# Arduino_AMRSID_tester_dual.net
KiCad netlist of a schematic drawn in EAGLE
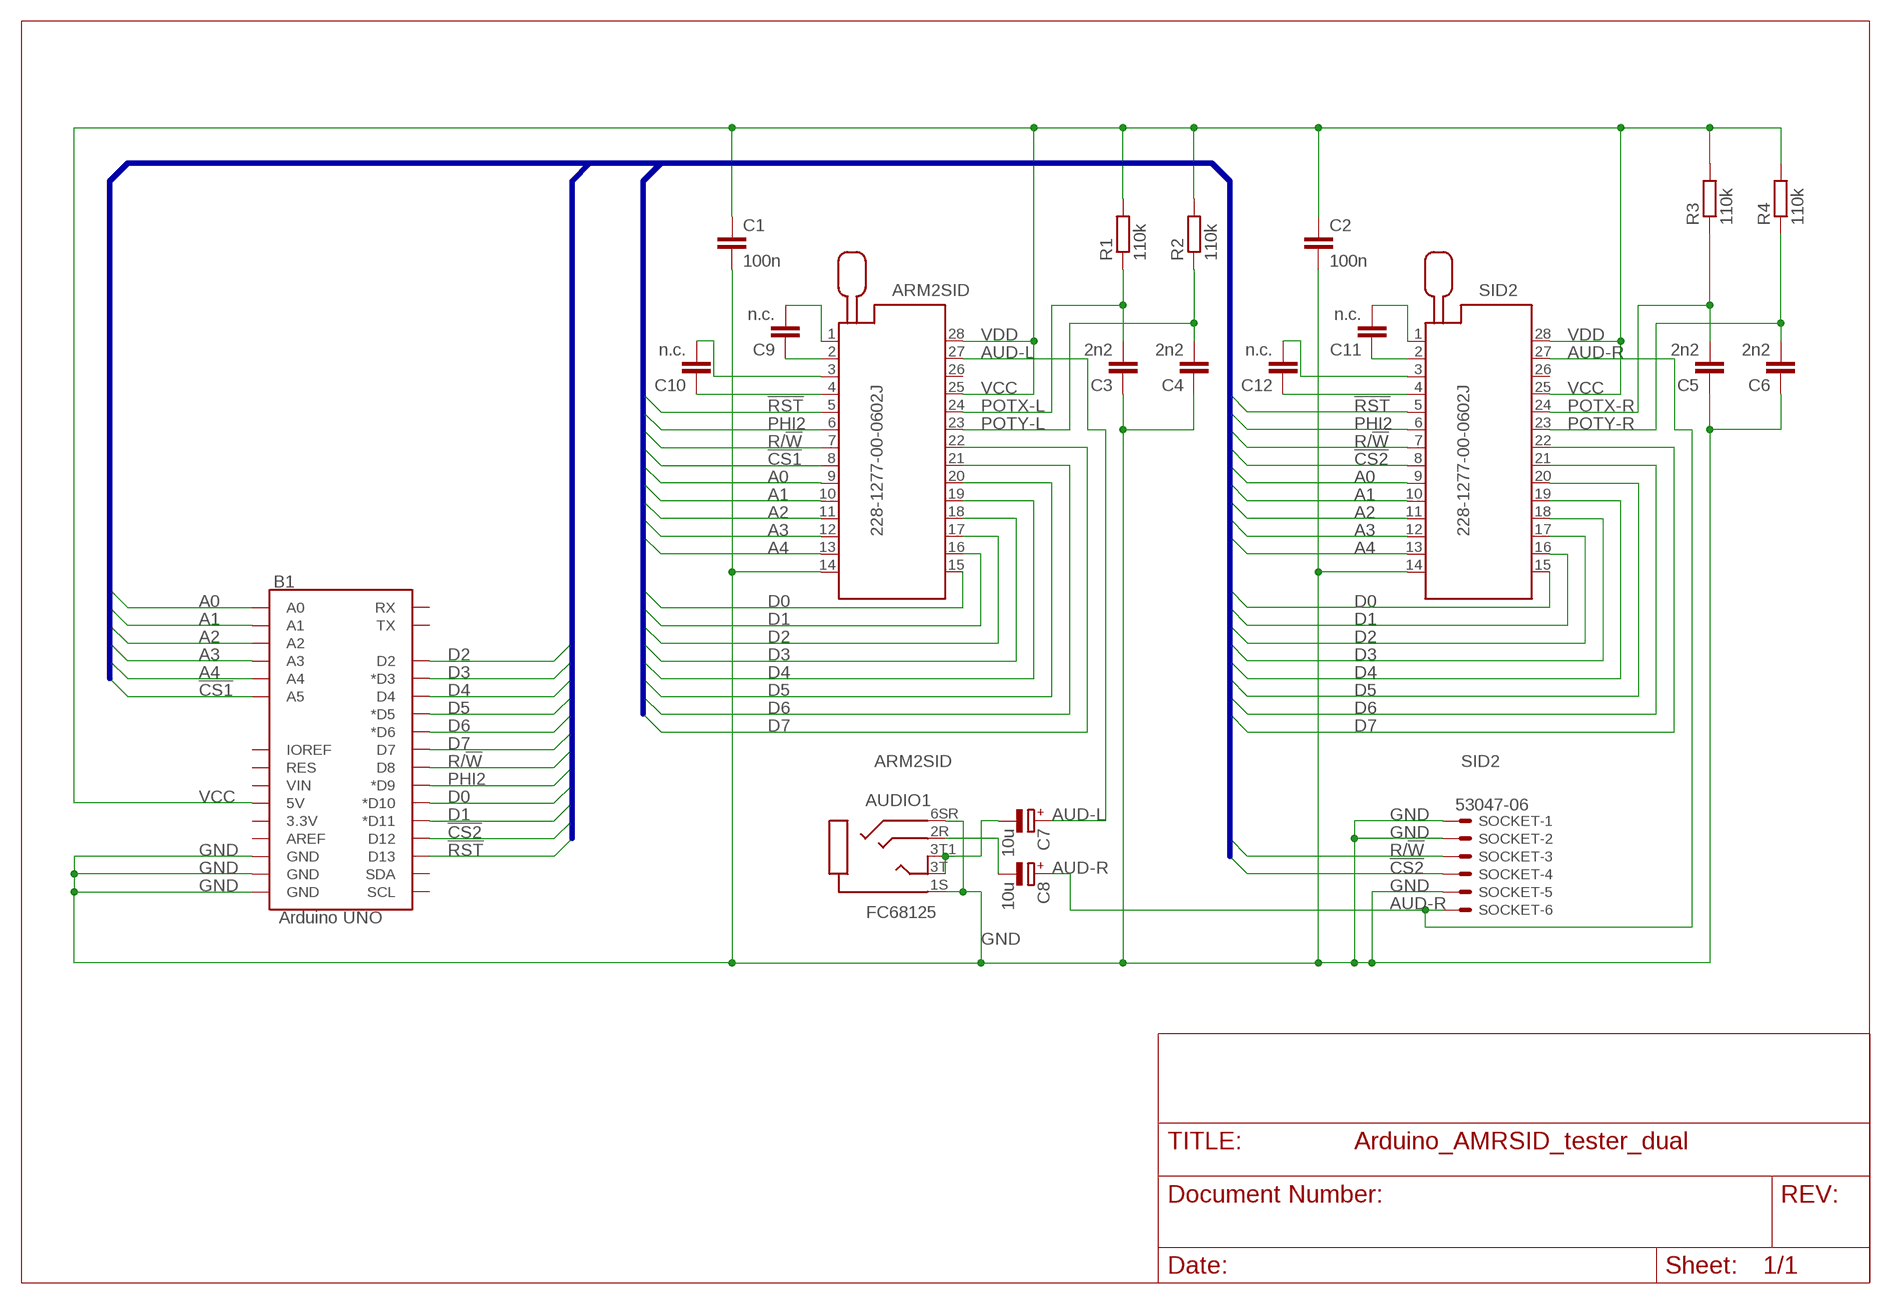
[diagram p0: schematic, sheet 1]

(export (version "E")
  (design (tool "Eeschema 10.0.6"))
  (components
    (comp (ref "ARM2SID")
      (value "228-1277-00-0602J")
      (footprint "eagle-import:228-1277-00-0602J")
      (fields (field (name "MF") "3M"))
      (libsource (lib "eagle-import") (part "228-?00-0602J1277-"))
    )
    (comp (ref "AUDIO1")
      (value "FC68125")
      (footprint "eagle-import:FC68125")
      (libsource (lib "eagle-import") (part "FC68125"))
    )
    (comp (ref "B1")
      (value "Arduino UNO")
      (footprint "eagle-import:UNO_R3_SHIELD")
      (libsource (lib "eagle-import") (part "ARDUINO_UNO_R3_SHIELDBASIC"))
    )
    (comp (ref "C1")
      (value "100n")
      (footprint "eagle-import:C0805K")
      (libsource (lib "eagle-import") (part "C-EUC0805K"))
    )
    (comp (ref "C2")
      (value "100n")
      (footprint "eagle-import:C0805K")
      (libsource (lib "eagle-import") (part "C-EUC0805K"))
    )
    (comp (ref "C3")
      (value "2n2")
      (footprint "eagle-import:C0805K")
      (libsource (lib "eagle-import") (part "C-EUC0805K"))
    )
    (comp (ref "C4")
      (value "2n2")
      (footprint "eagle-import:C0805K")
      (libsource (lib "eagle-import") (part "C-EUC0805K"))
    )
    (comp (ref "C5")
      (value "2n2")
      (footprint "eagle-import:C0805K")
      (libsource (lib "eagle-import") (part "C-EUC0805K"))
    )
    (comp (ref "C6")
      (value "2n2")
      (footprint "eagle-import:C0805K")
      (libsource (lib "eagle-import") (part "C-EUC0805K"))
    )
    (comp (ref "C7")
      (value "10u")
      (footprint "eagle-import:B_3528-21R")
      (libsource (lib "eagle-import") (part "CPOL-EUB/3528-21R"))
    )
    (comp (ref "C8")
      (value "10u")
      (footprint "eagle-import:B_3528-21R")
      (libsource (lib "eagle-import") (part "CPOL-EUB/3528-21R"))
    )
    (comp (ref "C9")
      (value "n.c.")
      (footprint "eagle-import:C0805K")
      (libsource (lib "eagle-import") (part "C-EUC0805K"))
    )
    (comp (ref "C10")
      (value "n.c.")
      (footprint "eagle-import:C0805K")
      (libsource (lib "eagle-import") (part "C-EUC0805K"))
    )
    (comp (ref "C11")
      (value "n.c.")
      (footprint "eagle-import:C0805K")
      (libsource (lib "eagle-import") (part "C-EUC0805K"))
    )
    (comp (ref "C12")
      (value "n.c.")
      (footprint "eagle-import:C0805K")
      (libsource (lib "eagle-import") (part "C-EUC0805K"))
    )
    (comp (ref "R1")
      (value "110k")
      (footprint "eagle-import:R0805")
      (libsource (lib "eagle-import") (part "R-EU_R0805"))
    )
    (comp (ref "R2")
      (value "110k")
      (footprint "eagle-import:R0805")
      (libsource (lib "eagle-import") (part "R-EU_R0805"))
    )
    (comp (ref "R3")
      (value "110k")
      (footprint "eagle-import:R0805")
      (libsource (lib "eagle-import") (part "R-EU_R0805"))
    )
    (comp (ref "R4")
      (value "110k")
      (footprint "eagle-import:R0805")
      (libsource (lib "eagle-import") (part "R-EU_R0805"))
    )
    (comp (ref "SID2")
      (value "228-1277-00-0602J")
      (footprint "eagle-import:228-1277-00-0602J")
      (fields (field (name "MF") "3M"))
      (libsource (lib "eagle-import") (part "228-?00-0602J1277-"))
    )
    (comp (ref "SOCKET")
      (value "53047-06")
      (footprint "eagle-import:53047-06")
      (fields (field (name "MPN") "53047-0610-C"))
      (libsource (lib "eagle-import") (part "53?-06047"))
    )
  )
  (nets
    (net (code "1") (name "/A0") (class "Default")
      (node (ref "ARM2SID") (pin "9") (pinfunction "9_9") (pintype "passive"))
      (node (ref "B1") (pin "A0") (pinfunction "A0_A0") (pintype "bidirectional"))
      (node (ref "SID2") (pin "9") (pinfunction "9_9") (pintype "passive"))
    )
    (net (code "2") (name "/A1") (class "Default")
      (node (ref "ARM2SID") (pin "10") (pinfunction "10_10") (pintype "passive"))
      (node (ref "B1") (pin "A1") (pinfunction "A1_A1") (pintype "bidirectional"))
      (node (ref "SID2") (pin "10") (pinfunction "10_10") (pintype "passive"))
    )
    (net (code "3") (name "/A2") (class "Default")
      (node (ref "ARM2SID") (pin "11") (pinfunction "11_11") (pintype "passive"))
      (node (ref "B1") (pin "A2") (pinfunction "A2_A2") (pintype "bidirectional"))
      (node (ref "SID2") (pin "11") (pinfunction "11_11") (pintype "passive"))
    )
    (net (code "4") (name "/A3") (class "Default")
      (node (ref "ARM2SID") (pin "12") (pinfunction "12_12") (pintype "passive"))
      (node (ref "B1") (pin "A3") (pinfunction "A3_A3") (pintype "bidirectional"))
      (node (ref "SID2") (pin "12") (pinfunction "12_12") (pintype "passive"))
    )
    (net (code "5") (name "/A4") (class "Default")
      (node (ref "ARM2SID") (pin "13") (pinfunction "13_13") (pintype "passive"))
      (node (ref "B1") (pin "A4") (pinfunction "A4_A4") (pintype "bidirectional"))
      (node (ref "SID2") (pin "13") (pinfunction "13_13") (pintype "passive"))
    )
    (net (code "6") (name "/AUD-L") (class "Default")
      (node (ref "ARM2SID") (pin "27") (pinfunction "27_27") (pintype "passive"))
      (node (ref "C7") (pin "+") (pinfunction "+_+") (pintype "passive"))
    )
    (net (code "7") (name "/AUD-R") (class "Default")
      (node (ref "C8") (pin "+") (pinfunction "+_+") (pintype "passive"))
      (node (ref "SID2") (pin "27") (pinfunction "27_27") (pintype "passive"))
      (node (ref "SOCKET") (pin "6") (pinfunction "S_6") (pintype "passive"))
    )
    (net (code "8") (name "/D0") (class "Default")
      (node (ref "ARM2SID") (pin "15") (pinfunction "15_15") (pintype "passive"))
      (node (ref "B1") (pin "D10") (pinfunction "*D10_D10") (pintype "bidirectional"))
      (node (ref "SID2") (pin "15") (pinfunction "15_15") (pintype "passive"))
    )
    (net (code "9") (name "/D1") (class "Default")
      (node (ref "ARM2SID") (pin "16") (pinfunction "16_16") (pintype "passive"))
      (node (ref "B1") (pin "D11") (pinfunction "*D11_D11") (pintype "bidirectional"))
      (node (ref "SID2") (pin "16") (pinfunction "16_16") (pintype "passive"))
    )
    (net (code "10") (name "/D2") (class "Default")
      (node (ref "ARM2SID") (pin "17") (pinfunction "17_17") (pintype "passive"))
      (node (ref "B1") (pin "D2") (pinfunction "D2_D2") (pintype "bidirectional"))
      (node (ref "SID2") (pin "17") (pinfunction "17_17") (pintype "passive"))
    )
    (net (code "11") (name "/D3") (class "Default")
      (node (ref "ARM2SID") (pin "18") (pinfunction "18_18") (pintype "passive"))
      (node (ref "B1") (pin "D3") (pinfunction "*D3_D3") (pintype "bidirectional"))
      (node (ref "SID2") (pin "18") (pinfunction "18_18") (pintype "passive"))
    )
    (net (code "12") (name "/D4") (class "Default")
      (node (ref "ARM2SID") (pin "19") (pinfunction "19_19") (pintype "passive"))
      (node (ref "B1") (pin "D4") (pinfunction "D4_D4") (pintype "bidirectional"))
      (node (ref "SID2") (pin "19") (pinfunction "19_19") (pintype "passive"))
    )
    (net (code "13") (name "/D5") (class "Default")
      (node (ref "ARM2SID") (pin "20") (pinfunction "20_20") (pintype "passive"))
      (node (ref "B1") (pin "D5") (pinfunction "*D5_D5") (pintype "bidirectional"))
      (node (ref "SID2") (pin "20") (pinfunction "20_20") (pintype "passive"))
    )
    (net (code "14") (name "/D6") (class "Default")
      (node (ref "ARM2SID") (pin "21") (pinfunction "21_21") (pintype "passive"))
      (node (ref "B1") (pin "D6") (pinfunction "*D6_D6") (pintype "bidirectional"))
      (node (ref "SID2") (pin "21") (pinfunction "21_21") (pintype "passive"))
    )
    (net (code "15") (name "/D7") (class "Default")
      (node (ref "ARM2SID") (pin "22") (pinfunction "22_22") (pintype "passive"))
      (node (ref "B1") (pin "D7") (pinfunction "D7_D7") (pintype "bidirectional"))
      (node (ref "SID2") (pin "22") (pinfunction "22_22") (pintype "passive"))
    )
    (net (code "16") (name "/GND") (class "Default")
      (node (ref "ARM2SID") (pin "14") (pinfunction "14_14") (pintype "passive"))
      (node (ref "AUDIO1") (pin "1S") (pinfunction "1S_1S") (pintype "bidirectional"))
      (node (ref "AUDIO1") (pin "6SR") (pinfunction "6SR_6SR") (pintype "bidirectional"))
      (node (ref "B1") (pin "GND@0") (pinfunction "GND_GND@0") (pintype "bidirectional"))
      (node (ref "B1") (pin "GND@1") (pinfunction "GND_GND@1") (pintype "bidirectional"))
      (node (ref "B1") (pin "GND@2") (pinfunction "GND_GND@2") (pintype "bidirectional"))
      (node (ref "C1") (pin "2") (pinfunction "2_2") (pintype "passive"))
      (node (ref "C2") (pin "2") (pinfunction "2_2") (pintype "passive"))
      (node (ref "C3") (pin "1") (pinfunction "1_1") (pintype "passive"))
      (node (ref "C4") (pin "1") (pinfunction "1_1") (pintype "passive"))
      (node (ref "C5") (pin "1") (pinfunction "1_1") (pintype "passive"))
      (node (ref "C6") (pin "1") (pinfunction "1_1") (pintype "passive"))
      (node (ref "SID2") (pin "14") (pinfunction "14_14") (pintype "passive"))
      (node (ref "SOCKET") (pin "1") (pinfunction "S_1") (pintype "passive"))
      (node (ref "SOCKET") (pin "2") (pinfunction "S_2") (pintype "passive"))
      (node (ref "SOCKET") (pin "5") (pinfunction "S_5") (pintype "passive"))
    )
    (net (code "17") (name "/PHI2") (class "Default")
      (node (ref "ARM2SID") (pin "6") (pinfunction "6_6") (pintype "passive"))
      (node (ref "B1") (pin "D9") (pinfunction "*D9_D9") (pintype "bidirectional"))
      (node (ref "SID2") (pin "6") (pinfunction "6_6") (pintype "passive"))
    )
    (net (code "18") (name "/POTX-L") (class "Default")
      (node (ref "ARM2SID") (pin "24") (pinfunction "24_24") (pintype "passive"))
      (node (ref "C3") (pin "2") (pinfunction "2_2") (pintype "passive"))
      (node (ref "R1") (pin "1") (pinfunction "1_1") (pintype "passive"))
    )
    (net (code "19") (name "/POTX-R") (class "Default")
      (node (ref "C5") (pin "2") (pinfunction "2_2") (pintype "passive"))
      (node (ref "R3") (pin "1") (pinfunction "1_1") (pintype "passive"))
      (node (ref "SID2") (pin "24") (pinfunction "24_24") (pintype "passive"))
    )
    (net (code "20") (name "/POTY-L") (class "Default")
      (node (ref "ARM2SID") (pin "23") (pinfunction "23_23") (pintype "passive"))
      (node (ref "C4") (pin "2") (pinfunction "2_2") (pintype "passive"))
      (node (ref "R2") (pin "1") (pinfunction "1_1") (pintype "passive"))
    )
    (net (code "21") (name "/POTY-R") (class "Default")
      (node (ref "C6") (pin "2") (pinfunction "2_2") (pintype "passive"))
      (node (ref "R4") (pin "1") (pinfunction "1_1") (pintype "passive"))
      (node (ref "SID2") (pin "23") (pinfunction "23_23") (pintype "passive"))
    )
    (net (code "22") (name "/R{slash}~{W}") (class "Default")
      (node (ref "ARM2SID") (pin "7") (pinfunction "7_7") (pintype "passive"))
      (node (ref "B1") (pin "D8") (pinfunction "D8_D8") (pintype "bidirectional"))
      (node (ref "SID2") (pin "7") (pinfunction "7_7") (pintype "passive"))
      (node (ref "SOCKET") (pin "3") (pinfunction "S_3") (pintype "passive"))
    )
    (net (code "23") (name "/VCC") (class "Default")
      (node (ref "ARM2SID") (pin "25") (pinfunction "25_25") (pintype "passive"))
      (node (ref "ARM2SID") (pin "28") (pinfunction "28_28") (pintype "passive"))
      (node (ref "B1") (pin "5V") (pinfunction "5V_5V") (pintype "bidirectional"))
      (node (ref "C1") (pin "1") (pinfunction "1_1") (pintype "passive"))
      (node (ref "C2") (pin "1") (pinfunction "1_1") (pintype "passive"))
      (node (ref "R1") (pin "2") (pinfunction "2_2") (pintype "passive"))
      (node (ref "R2") (pin "2") (pinfunction "2_2") (pintype "passive"))
      (node (ref "R3") (pin "2") (pinfunction "2_2") (pintype "passive"))
      (node (ref "R4") (pin "2") (pinfunction "2_2") (pintype "passive"))
      (node (ref "SID2") (pin "25") (pinfunction "25_25") (pintype "passive"))
      (node (ref "SID2") (pin "28") (pinfunction "28_28") (pintype "passive"))
    )
    (net (code "24") (name "/~{CS1}") (class "Default")
      (node (ref "ARM2SID") (pin "8") (pinfunction "8_8") (pintype "passive"))
      (node (ref "B1") (pin "A5") (pinfunction "A5_A5") (pintype "bidirectional"))
    )
    (net (code "25") (name "/~{CS2}") (class "Default")
      (node (ref "B1") (pin "D12") (pinfunction "D12_D12") (pintype "bidirectional"))
      (node (ref "SID2") (pin "8") (pinfunction "8_8") (pintype "passive"))
      (node (ref "SOCKET") (pin "4") (pinfunction "S_4") (pintype "passive"))
    )
    (net (code "26") (name "/~{RST}") (class "Default")
      (node (ref "ARM2SID") (pin "5") (pinfunction "5_5") (pintype "passive"))
      (node (ref "B1") (pin "D13") (pinfunction "D13_D13") (pintype "bidirectional"))
      (node (ref "SID2") (pin "5") (pinfunction "5_5") (pintype "passive"))
    )
    (net (code "27") (name "Net-(ARM2SID-Pad1)") (class "Default")
      (node (ref "ARM2SID") (pin "1") (pinfunction "1_1") (pintype "passive"))
      (node (ref "C9") (pin "2") (pinfunction "2_2") (pintype "passive"))
    )
    (net (code "28") (name "Net-(ARM2SID-Pad2)") (class "Default")
      (node (ref "ARM2SID") (pin "2") (pinfunction "2_2") (pintype "passive"))
      (node (ref "C9") (pin "1") (pinfunction "1_1") (pintype "passive"))
    )
    (net (code "29") (name "Net-(ARM2SID-Pad3)") (class "Default")
      (node (ref "ARM2SID") (pin "3") (pinfunction "3_3") (pintype "passive"))
      (node (ref "C10") (pin "2") (pinfunction "2_2") (pintype "passive"))
    )
    (net (code "30") (name "Net-(ARM2SID-Pad4)") (class "Default")
      (node (ref "ARM2SID") (pin "4") (pinfunction "4_4") (pintype "passive"))
      (node (ref "C10") (pin "1") (pinfunction "1_1") (pintype "passive"))
    )
    (net (code "31") (name "Net-(AUDIO1-Pad2R)") (class "Default")
      (node (ref "AUDIO1") (pin "2R") (pinfunction "2R_2R") (pintype "bidirectional"))
      (node (ref "C8") (pin "-") (pinfunction "-_-") (pintype "passive"))
    )
    (net (code "32") (name "Net-(AUDIO1-Pad3T)") (class "Default")
      (node (ref "AUDIO1") (pin "3T") (pinfunction "3T_3T") (pintype "bidirectional"))
      (node (ref "AUDIO1") (pin "3T1") (pinfunction "3T1_3T1") (pintype "bidirectional"))
      (node (ref "C7") (pin "-") (pinfunction "-_-") (pintype "passive"))
    )
    (net (code "33") (name "Net-(C11-Pad1)") (class "Default")
      (node (ref "C11") (pin "1") (pinfunction "1_1") (pintype "passive"))
      (node (ref "SID2") (pin "2") (pinfunction "2_2") (pintype "passive"))
    )
    (net (code "34") (name "Net-(C11-Pad2)") (class "Default")
      (node (ref "C11") (pin "2") (pinfunction "2_2") (pintype "passive"))
      (node (ref "SID2") (pin "1") (pinfunction "1_1") (pintype "passive"))
    )
    (net (code "35") (name "Net-(C12-Pad1)") (class "Default")
      (node (ref "C12") (pin "1") (pinfunction "1_1") (pintype "passive"))
      (node (ref "SID2") (pin "4") (pinfunction "4_4") (pintype "passive"))
    )
    (net (code "36") (name "Net-(C12-Pad2)") (class "Default")
      (node (ref "C12") (pin "2") (pinfunction "2_2") (pintype "passive"))
      (node (ref "SID2") (pin "3") (pinfunction "3_3") (pintype "passive"))
    )
    (net (code "37") (name "unconnected-(ARM2SID-Pad26)") (class "Default")
      (node (ref "ARM2SID") (pin "26") (pinfunction "26_26") (pintype "passive"))
    )
    (net (code "38") (name "unconnected-(B1-Pad3.3V)") (class "Default")
      (node (ref "B1") (pin "3.3V") (pinfunction "3.3V_3.3V") (pintype "bidirectional"))
    )
    (net (code "39") (name "unconnected-(B1-PadAREF)") (class "Default")
      (node (ref "B1") (pin "AREF") (pinfunction "AREF_AREF") (pintype "bidirectional"))
    )
    (net (code "40") (name "unconnected-(B1-PadIOREF)") (class "Default")
      (node (ref "B1") (pin "IOREF") (pinfunction "IOREF_IOREF") (pintype "bidirectional"))
    )
    (net (code "41") (name "unconnected-(B1-PadRES)") (class "Default")
      (node (ref "B1") (pin "RES") (pinfunction "RES_RES") (pintype "bidirectional"))
    )
    (net (code "42") (name "unconnected-(B1-PadRX)") (class "Default")
      (node (ref "B1") (pin "RX") (pinfunction "RX_RX") (pintype "bidirectional"))
    )
    (net (code "43") (name "unconnected-(B1-PadSCL)") (class "Default")
      (node (ref "B1") (pin "SCL") (pinfunction "SCL_SCL") (pintype "bidirectional"))
    )
    (net (code "44") (name "unconnected-(B1-PadSDA)") (class "Default")
      (node (ref "B1") (pin "SDA") (pinfunction "SDA_SDA") (pintype "bidirectional"))
    )
    (net (code "45") (name "unconnected-(B1-PadTX)") (class "Default")
      (node (ref "B1") (pin "TX") (pinfunction "TX_TX") (pintype "bidirectional"))
    )
    (net (code "46") (name "unconnected-(B1-PadVIN)") (class "Default")
      (node (ref "B1") (pin "VIN") (pinfunction "VIN_VIN") (pintype "bidirectional"))
    )
    (net (code "47") (name "unconnected-(SID2-Pad26)") (class "Default")
      (node (ref "SID2") (pin "26") (pinfunction "26_26") (pintype "passive"))
    )
  )
)
